# FollowerCounter_60mm_v010.net
KiCad netlist of a schematic drawn in EAGLE
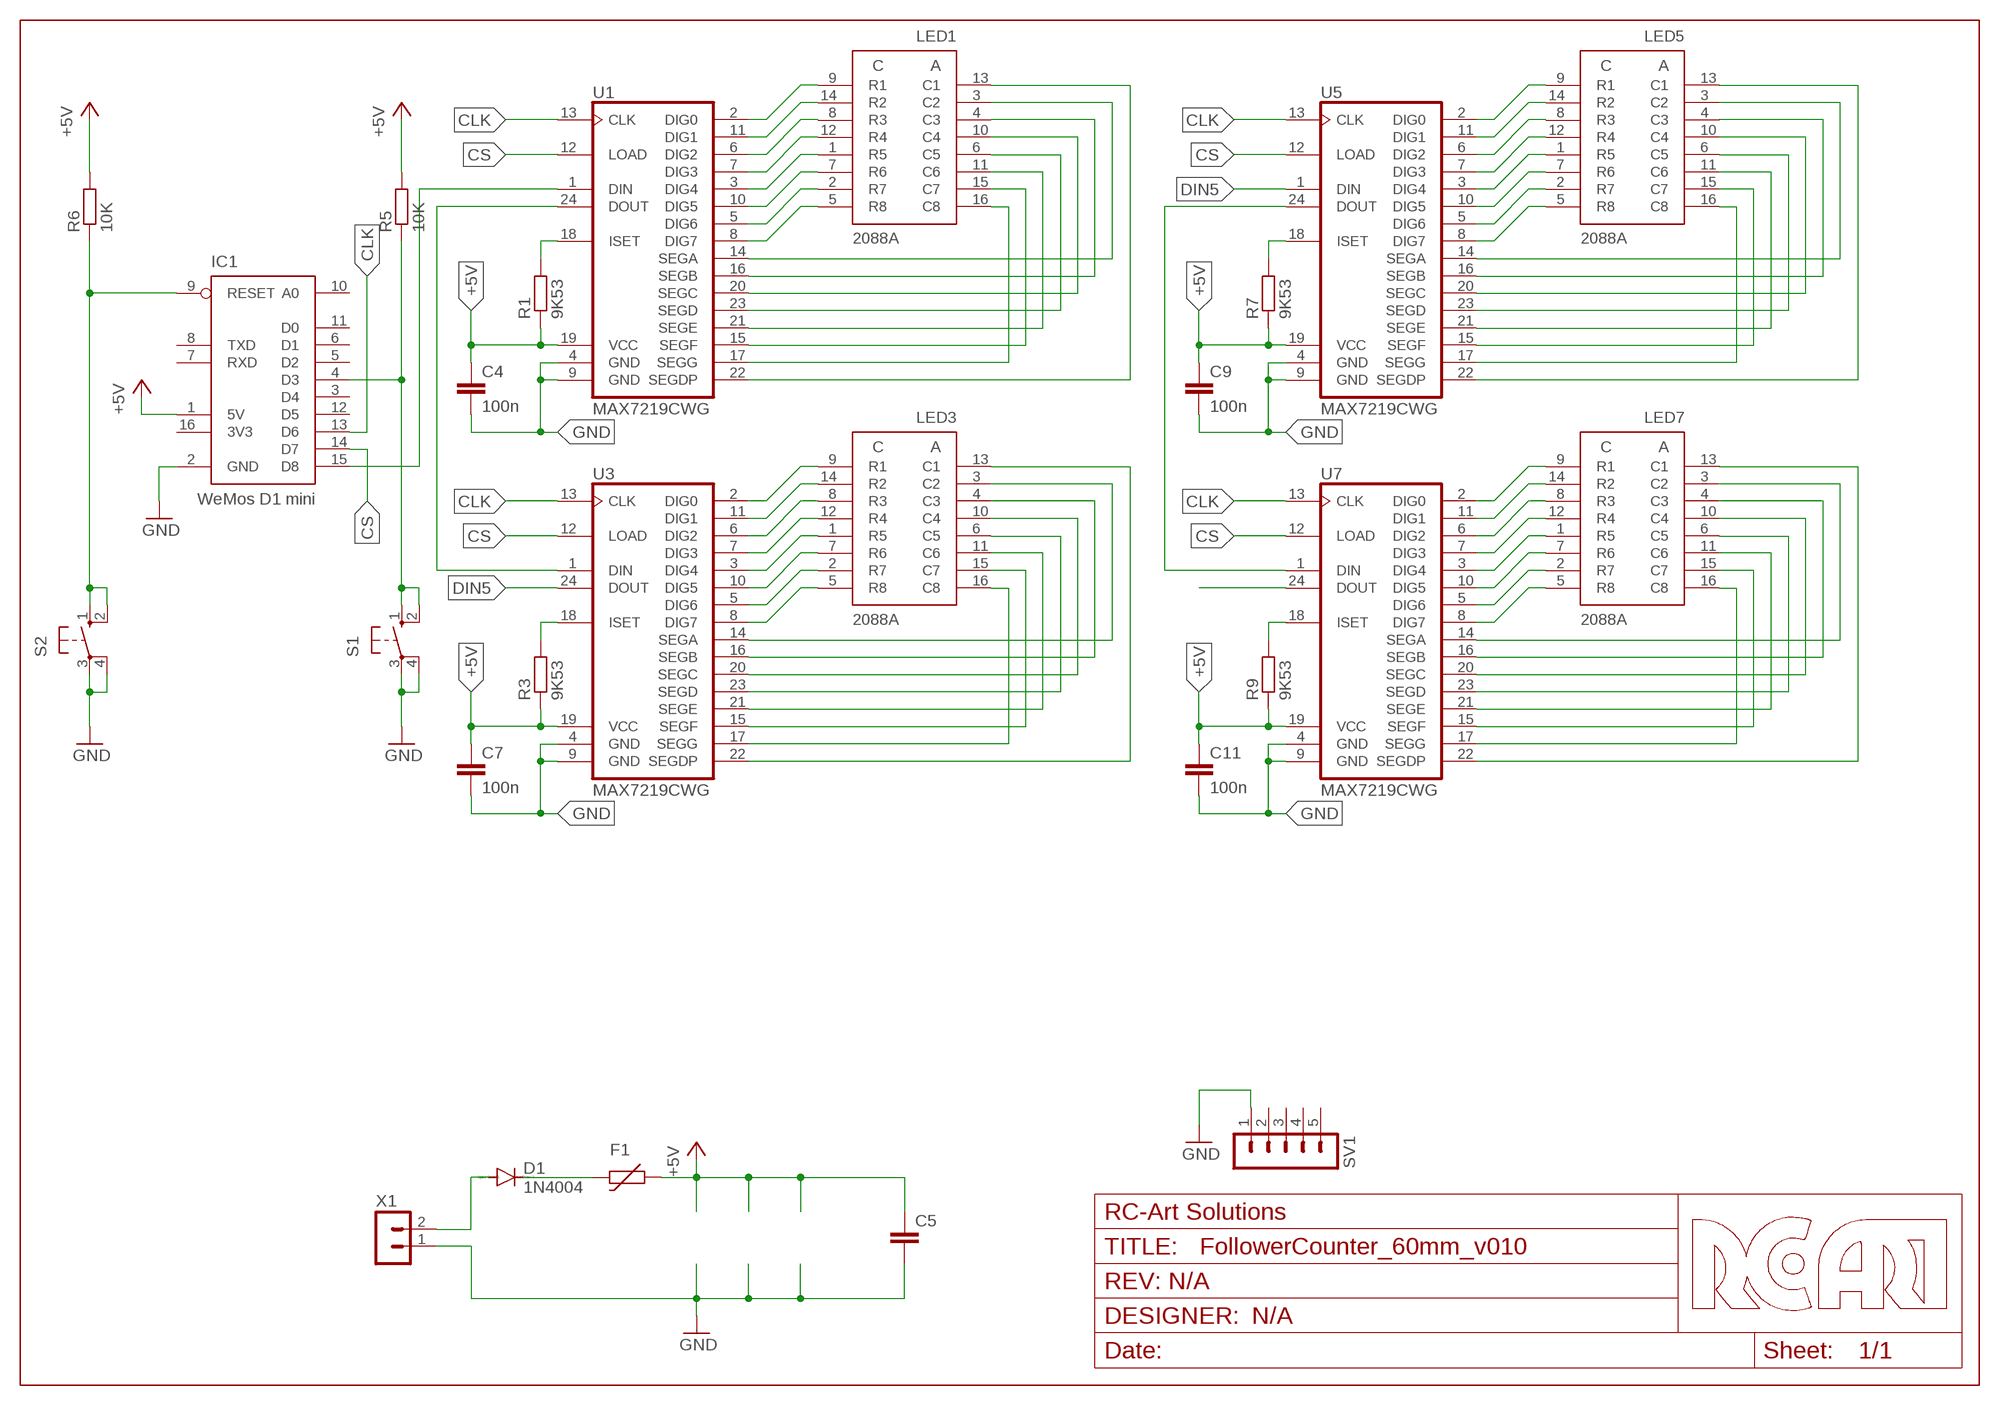
[diagram p0: schematic, sheet 1]

(export (version "E")
  (design (tool "Eeschema 10.0.6"))
  (components
    (comp (ref "C4")
      (value "100n")
      (footprint "eagle-import:C0805")
      (libsource (lib "eagle-import") (part "C-EUC0805"))
    )
    (comp (ref "C5")
      (value "C-EUC0805")
      (footprint "eagle-import:C0805")
      (libsource (lib "eagle-import") (part "C-EUC0805"))
    )
    (comp (ref "C7")
      (value "100n")
      (footprint "eagle-import:C0805")
      (libsource (lib "eagle-import") (part "C-EUC0805"))
    )
    (comp (ref "C9")
      (value "100n")
      (footprint "eagle-import:C0805")
      (libsource (lib "eagle-import") (part "C-EUC0805"))
    )
    (comp (ref "C11")
      (value "100n")
      (footprint "eagle-import:C0805")
      (libsource (lib "eagle-import") (part "C-EUC0805"))
    )
    (comp (ref "D1")
      (value "1N4004")
      (footprint "eagle-import:DO41-10")
      (libsource (lib "eagle-import") (part "1N4004"))
    )
    (comp (ref "F1")
      (value "MF-MSMF075/24-EU")
      (footprint "eagle-import:1812")
      (fields (field (name "MANUFACTURER") "Bourns Inc.") (field (name "PART_NUMBER") "MF-MSMF075/24-2"))
      (libsource (lib "eagle-import") (part "MF-MSMF?-EU075/24"))
    )
    (comp (ref "FRAME1")
      (value "MF_FRAMEDEFAULT")
      (footprint "eagle-import:MF_FRAME_DEFAULT")
      (fields (field (name "REVNUM") "REV: N/A") (field (name "DNAME") "N/A") (field (name "HOUSEPART") "0"))
      (libsource (lib "eagle-import") (part "MF_FRAMEDEFAULT"))
    )
    (comp (ref "IC1")
      (value "WeMos D1 mini")
      (footprint "eagle-import:D1_MINI")
      (libsource (lib "eagle-import") (part "D1_MINI"))
    )
    (comp (ref "LED1")
      (value "2088A")
      (footprint "eagle-import:8X8_60X60")
      (libsource (lib "eagle-import") (part "2088A"))
    )
    (comp (ref "LED3")
      (value "2088A")
      (footprint "eagle-import:8X8_60X60")
      (libsource (lib "eagle-import") (part "2088A"))
    )
    (comp (ref "LED5")
      (value "2088A")
      (footprint "eagle-import:8X8_60X60")
      (libsource (lib "eagle-import") (part "2088A"))
    )
    (comp (ref "LED7")
      (value "2088A")
      (footprint "eagle-import:8X8_60X60")
      (libsource (lib "eagle-import") (part "2088A"))
    )
    (comp (ref "R1")
      (value "9K53")
      (footprint "eagle-import:R0805")
      (libsource (lib "eagle-import") (part "R-EU_R0805"))
    )
    (comp (ref "R3")
      (value "9K53")
      (footprint "eagle-import:R0805")
      (libsource (lib "eagle-import") (part "R-EU_R0805"))
    )
    (comp (ref "R5")
      (value "10K")
      (footprint "eagle-import:R0805")
      (libsource (lib "eagle-import") (part "R-EU_R0805"))
    )
    (comp (ref "R6")
      (value "10K")
      (footprint "eagle-import:R0805")
      (libsource (lib "eagle-import") (part "R-EU_R0805"))
    )
    (comp (ref "R7")
      (value "9K53")
      (footprint "eagle-import:R0805")
      (libsource (lib "eagle-import") (part "R-EU_R0805"))
    )
    (comp (ref "R9")
      (value "9K53")
      (footprint "eagle-import:R0805")
      (libsource (lib "eagle-import") (part "R-EU_R0805"))
    )
    (comp (ref "S1")
      (value "10-XXS")
      (footprint "eagle-import:B3FS-10XX")
      (libsource (lib "eagle-import") (part "10-XXS"))
    )
    (comp (ref "S2")
      (value "10-XXS")
      (footprint "eagle-import:B3FS-10XX")
      (libsource (lib "eagle-import") (part "10-XXS"))
    )
    (comp (ref "SV1")
      (value "MA05-1")
      (footprint "eagle-import:MA05-1")
      (libsource (lib "eagle-import") (part "MA05-1"))
    )
    (comp (ref "U1")
      (value "MAX7219CWG")
      (footprint "eagle-import:SO24L")
      (libsource (lib "eagle-import") (part "MAX7219CWG"))
    )
    (comp (ref "U3")
      (value "MAX7219CWG")
      (footprint "eagle-import:SO24L")
      (libsource (lib "eagle-import") (part "MAX7219CWG"))
    )
    (comp (ref "U5")
      (value "MAX7219CWG")
      (footprint "eagle-import:SO24L")
      (libsource (lib "eagle-import") (part "MAX7219CWG"))
    )
    (comp (ref "U7")
      (value "MAX7219CWG")
      (footprint "eagle-import:SO24L")
      (libsource (lib "eagle-import") (part "MAX7219CWG"))
    )
    (comp (ref "X1")
      (value "MA02-1")
      (footprint "eagle-import:MA02-1")
      (libsource (lib "eagle-import") (part "MA02-1"))
    )
  )
  (nets
    (net (code "1") (name "+5V") (class "Default")
      (node (ref "C11") (pin "1") (pinfunction "1_1") (pintype "passive"))
      (node (ref "C4") (pin "1") (pinfunction "1_1") (pintype "passive"))
      (node (ref "C5") (pin "1") (pinfunction "1_1") (pintype "passive"))
      (node (ref "C7") (pin "1") (pinfunction "1_1") (pintype "passive"))
      (node (ref "C9") (pin "1") (pinfunction "1_1") (pintype "passive"))
      (node (ref "F1") (pin "1") (pinfunction "1_1") (pintype "passive"))
      (node (ref "IC1") (pin "1") (pinfunction "5V_1") (pintype "bidirectional"))
      (node (ref "R1") (pin "1") (pinfunction "1_1") (pintype "passive"))
      (node (ref "R3") (pin "1") (pinfunction "1_1") (pintype "passive"))
      (node (ref "R5") (pin "2") (pinfunction "2_2") (pintype "passive"))
      (node (ref "R6") (pin "2") (pinfunction "2_2") (pintype "passive"))
      (node (ref "R7") (pin "1") (pinfunction "1_1") (pintype "passive"))
      (node (ref "R9") (pin "1") (pinfunction "1_1") (pintype "passive"))
      (node (ref "U1") (pin "19") (pinfunction "VCC_19") (pintype "power_in"))
      (node (ref "U3") (pin "19") (pinfunction "VCC_19") (pintype "power_in"))
      (node (ref "U5") (pin "19") (pinfunction "VCC_19") (pintype "power_in"))
      (node (ref "U7") (pin "19") (pinfunction "VCC_19") (pintype "power_in"))
    )
    (net (code "2") (name "CLK") (class "Default")
      (node (ref "IC1") (pin "13") (pinfunction "D6_13") (pintype "bidirectional"))
      (node (ref "U1") (pin "13") (pinfunction "CLK_13") (pintype "input"))
      (node (ref "U3") (pin "13") (pinfunction "CLK_13") (pintype "input"))
      (node (ref "U5") (pin "13") (pinfunction "CLK_13") (pintype "input"))
      (node (ref "U7") (pin "13") (pinfunction "CLK_13") (pintype "input"))
    )
    (net (code "3") (name "CS") (class "Default")
      (node (ref "IC1") (pin "14") (pinfunction "D7_14") (pintype "bidirectional"))
      (node (ref "U1") (pin "12") (pinfunction "LOAD_12") (pintype "input"))
      (node (ref "U3") (pin "12") (pinfunction "LOAD_12") (pintype "input"))
      (node (ref "U5") (pin "12") (pinfunction "LOAD_12") (pintype "input"))
      (node (ref "U7") (pin "12") (pinfunction "LOAD_12") (pintype "input"))
    )
    (net (code "4") (name "DIN5") (class "Default")
      (node (ref "U3") (pin "24") (pinfunction "DOUT_24") (pintype "output"))
      (node (ref "U5") (pin "1") (pinfunction "DIN_1") (pintype "input"))
    )
    (net (code "5") (name "GND") (class "Default")
      (node (ref "C11") (pin "2") (pinfunction "2_2") (pintype "passive"))
      (node (ref "C4") (pin "2") (pinfunction "2_2") (pintype "passive"))
      (node (ref "C5") (pin "2") (pinfunction "2_2") (pintype "passive"))
      (node (ref "C7") (pin "2") (pinfunction "2_2") (pintype "passive"))
      (node (ref "C9") (pin "2") (pinfunction "2_2") (pintype "passive"))
      (node (ref "IC1") (pin "2") (pinfunction "GND_2") (pintype "bidirectional"))
      (node (ref "S1") (pin "3") (pinfunction "P_3") (pintype "passive"))
      (node (ref "S1") (pin "4") (pinfunction "P1_4") (pintype "passive"))
      (node (ref "S2") (pin "3") (pinfunction "P_3") (pintype "passive"))
      (node (ref "S2") (pin "4") (pinfunction "P1_4") (pintype "passive"))
      (node (ref "SV1") (pin "1") (pinfunction "1_1") (pintype "passive"))
      (node (ref "U1") (pin "4") (pinfunction "GND_4") (pintype "power_in"))
      (node (ref "U1") (pin "9") (pinfunction "GND_9") (pintype "power_in"))
      (node (ref "U3") (pin "4") (pinfunction "GND_4") (pintype "power_in"))
      (node (ref "U3") (pin "9") (pinfunction "GND_9") (pintype "power_in"))
      (node (ref "U5") (pin "4") (pinfunction "GND_4") (pintype "power_in"))
      (node (ref "U5") (pin "9") (pinfunction "GND_9") (pintype "power_in"))
      (node (ref "U7") (pin "4") (pinfunction "GND_4") (pintype "power_in"))
      (node (ref "U7") (pin "9") (pinfunction "GND_9") (pintype "power_in"))
      (node (ref "X1") (pin "1") (pinfunction "1_1") (pintype "passive"))
    )
    (net (code "6") (name "Net-(D1-PadA)") (class "Default")
      (node (ref "D1") (pin "A") (pinfunction "A_A") (pintype "passive"))
      (node (ref "X1") (pin "2") (pinfunction "2_2") (pintype "passive"))
    )
    (net (code "7") (name "Net-(D1-PadC)") (class "Default")
      (node (ref "D1") (pin "C") (pinfunction "C_C") (pintype "passive"))
      (node (ref "F1") (pin "2") (pinfunction "2_2") (pintype "passive"))
    )
    (net (code "8") (name "Net-(IC1-D3)") (class "Default")
      (node (ref "IC1") (pin "4") (pinfunction "D3_4") (pintype "bidirectional"))
      (node (ref "R5") (pin "1") (pinfunction "1_1") (pintype "passive"))
      (node (ref "S1") (pin "1") (pinfunction "S_1") (pintype "passive"))
      (node (ref "S1") (pin "2") (pinfunction "S1_2") (pintype "passive"))
    )
    (net (code "9") (name "Net-(IC1-D8)") (class "Default")
      (node (ref "IC1") (pin "15") (pinfunction "D8_15") (pintype "bidirectional"))
      (node (ref "U1") (pin "1") (pinfunction "DIN_1") (pintype "input"))
    )
    (net (code "10") (name "Net-(IC1-RESET)") (class "Default")
      (node (ref "IC1") (pin "9") (pinfunction "RESET_9") (pintype "bidirectional"))
      (node (ref "R6") (pin "1") (pinfunction "1_1") (pintype "passive"))
      (node (ref "S2") (pin "1") (pinfunction "S_1") (pintype "passive"))
      (node (ref "S2") (pin "2") (pinfunction "S1_2") (pintype "passive"))
    )
    (net (code "11") (name "Net-(LED1-C1)") (class "Default")
      (node (ref "LED1") (pin "13") (pinfunction "C1_13") (pintype "bidirectional"))
      (node (ref "U1") (pin "22") (pinfunction "SEGDP_22") (pintype "output"))
    )
    (net (code "12") (name "Net-(LED1-C2)") (class "Default")
      (node (ref "LED1") (pin "3") (pinfunction "C2_3") (pintype "bidirectional"))
      (node (ref "U1") (pin "14") (pinfunction "SEGA_14") (pintype "output"))
    )
    (net (code "13") (name "Net-(LED1-C3)") (class "Default")
      (node (ref "LED1") (pin "4") (pinfunction "C3_4") (pintype "bidirectional"))
      (node (ref "U1") (pin "16") (pinfunction "SEGB_16") (pintype "output"))
    )
    (net (code "14") (name "Net-(LED1-C4)") (class "Default")
      (node (ref "LED1") (pin "10") (pinfunction "C4_10") (pintype "bidirectional"))
      (node (ref "U1") (pin "20") (pinfunction "SEGC_20") (pintype "output"))
    )
    (net (code "15") (name "Net-(LED1-C5)") (class "Default")
      (node (ref "LED1") (pin "6") (pinfunction "C5_6") (pintype "bidirectional"))
      (node (ref "U1") (pin "23") (pinfunction "SEGD_23") (pintype "output"))
    )
    (net (code "16") (name "Net-(LED1-C6)") (class "Default")
      (node (ref "LED1") (pin "11") (pinfunction "C6_11") (pintype "bidirectional"))
      (node (ref "U1") (pin "21") (pinfunction "SEGE_21") (pintype "output"))
    )
    (net (code "17") (name "Net-(LED1-C7)") (class "Default")
      (node (ref "LED1") (pin "15") (pinfunction "C7_15") (pintype "bidirectional"))
      (node (ref "U1") (pin "15") (pinfunction "SEGF_15") (pintype "output"))
    )
    (net (code "18") (name "Net-(LED1-C8)") (class "Default")
      (node (ref "LED1") (pin "16") (pinfunction "C8_16") (pintype "bidirectional"))
      (node (ref "U1") (pin "17") (pinfunction "SEGG_17") (pintype "output"))
    )
    (net (code "19") (name "Net-(LED1-R1)") (class "Default")
      (node (ref "LED1") (pin "9") (pinfunction "R1_9") (pintype "bidirectional"))
      (node (ref "U1") (pin "2") (pinfunction "DIG0_2") (pintype "output"))
    )
    (net (code "20") (name "Net-(LED1-R2)") (class "Default")
      (node (ref "LED1") (pin "14") (pinfunction "R2_14") (pintype "bidirectional"))
      (node (ref "U1") (pin "11") (pinfunction "DIG1_11") (pintype "output"))
    )
    (net (code "21") (name "Net-(LED1-R3)") (class "Default")
      (node (ref "LED1") (pin "8") (pinfunction "R3_8") (pintype "bidirectional"))
      (node (ref "U1") (pin "6") (pinfunction "DIG2_6") (pintype "output"))
    )
    (net (code "22") (name "Net-(LED1-R4)") (class "Default")
      (node (ref "LED1") (pin "12") (pinfunction "R4_12") (pintype "bidirectional"))
      (node (ref "U1") (pin "7") (pinfunction "DIG3_7") (pintype "output"))
    )
    (net (code "23") (name "Net-(LED1-R5)") (class "Default")
      (node (ref "LED1") (pin "1") (pinfunction "R5_1") (pintype "bidirectional"))
      (node (ref "U1") (pin "3") (pinfunction "DIG4_3") (pintype "output"))
    )
    (net (code "24") (name "Net-(LED1-R6)") (class "Default")
      (node (ref "LED1") (pin "7") (pinfunction "R6_7") (pintype "bidirectional"))
      (node (ref "U1") (pin "10") (pinfunction "DIG5_10") (pintype "output"))
    )
    (net (code "25") (name "Net-(LED1-R7)") (class "Default")
      (node (ref "LED1") (pin "2") (pinfunction "R7_2") (pintype "bidirectional"))
      (node (ref "U1") (pin "5") (pinfunction "DIG6_5") (pintype "output"))
    )
    (net (code "26") (name "Net-(LED1-R8)") (class "Default")
      (node (ref "LED1") (pin "5") (pinfunction "R8_5") (pintype "bidirectional"))
      (node (ref "U1") (pin "8") (pinfunction "DIG7_8") (pintype "output"))
    )
    (net (code "27") (name "Net-(LED3-C1)") (class "Default")
      (node (ref "LED3") (pin "13") (pinfunction "C1_13") (pintype "bidirectional"))
      (node (ref "U3") (pin "22") (pinfunction "SEGDP_22") (pintype "output"))
    )
    (net (code "28") (name "Net-(LED3-C2)") (class "Default")
      (node (ref "LED3") (pin "3") (pinfunction "C2_3") (pintype "bidirectional"))
      (node (ref "U3") (pin "14") (pinfunction "SEGA_14") (pintype "output"))
    )
    (net (code "29") (name "Net-(LED3-C3)") (class "Default")
      (node (ref "LED3") (pin "4") (pinfunction "C3_4") (pintype "bidirectional"))
      (node (ref "U3") (pin "16") (pinfunction "SEGB_16") (pintype "output"))
    )
    (net (code "30") (name "Net-(LED3-C4)") (class "Default")
      (node (ref "LED3") (pin "10") (pinfunction "C4_10") (pintype "bidirectional"))
      (node (ref "U3") (pin "20") (pinfunction "SEGC_20") (pintype "output"))
    )
    (net (code "31") (name "Net-(LED3-C5)") (class "Default")
      (node (ref "LED3") (pin "6") (pinfunction "C5_6") (pintype "bidirectional"))
      (node (ref "U3") (pin "23") (pinfunction "SEGD_23") (pintype "output"))
    )
    (net (code "32") (name "Net-(LED3-C6)") (class "Default")
      (node (ref "LED3") (pin "11") (pinfunction "C6_11") (pintype "bidirectional"))
      (node (ref "U3") (pin "21") (pinfunction "SEGE_21") (pintype "output"))
    )
    (net (code "33") (name "Net-(LED3-C7)") (class "Default")
      (node (ref "LED3") (pin "15") (pinfunction "C7_15") (pintype "bidirectional"))
      (node (ref "U3") (pin "15") (pinfunction "SEGF_15") (pintype "output"))
    )
    (net (code "34") (name "Net-(LED3-C8)") (class "Default")
      (node (ref "LED3") (pin "16") (pinfunction "C8_16") (pintype "bidirectional"))
      (node (ref "U3") (pin "17") (pinfunction "SEGG_17") (pintype "output"))
    )
    (net (code "35") (name "Net-(LED3-R1)") (class "Default")
      (node (ref "LED3") (pin "9") (pinfunction "R1_9") (pintype "bidirectional"))
      (node (ref "U3") (pin "2") (pinfunction "DIG0_2") (pintype "output"))
    )
    (net (code "36") (name "Net-(LED3-R2)") (class "Default")
      (node (ref "LED3") (pin "14") (pinfunction "R2_14") (pintype "bidirectional"))
      (node (ref "U3") (pin "11") (pinfunction "DIG1_11") (pintype "output"))
    )
    (net (code "37") (name "Net-(LED3-R3)") (class "Default")
      (node (ref "LED3") (pin "8") (pinfunction "R3_8") (pintype "bidirectional"))
      (node (ref "U3") (pin "6") (pinfunction "DIG2_6") (pintype "output"))
    )
    (net (code "38") (name "Net-(LED3-R4)") (class "Default")
      (node (ref "LED3") (pin "12") (pinfunction "R4_12") (pintype "bidirectional"))
      (node (ref "U3") (pin "7") (pinfunction "DIG3_7") (pintype "output"))
    )
    (net (code "39") (name "Net-(LED3-R5)") (class "Default")
      (node (ref "LED3") (pin "1") (pinfunction "R5_1") (pintype "bidirectional"))
      (node (ref "U3") (pin "3") (pinfunction "DIG4_3") (pintype "output"))
    )
    (net (code "40") (name "Net-(LED3-R6)") (class "Default")
      (node (ref "LED3") (pin "7") (pinfunction "R6_7") (pintype "bidirectional"))
      (node (ref "U3") (pin "10") (pinfunction "DIG5_10") (pintype "output"))
    )
    (net (code "41") (name "Net-(LED3-R7)") (class "Default")
      (node (ref "LED3") (pin "2") (pinfunction "R7_2") (pintype "bidirectional"))
      (node (ref "U3") (pin "5") (pinfunction "DIG6_5") (pintype "output"))
    )
    (net (code "42") (name "Net-(LED3-R8)") (class "Default")
      (node (ref "LED3") (pin "5") (pinfunction "R8_5") (pintype "bidirectional"))
      (node (ref "U3") (pin "8") (pinfunction "DIG7_8") (pintype "output"))
    )
    (net (code "43") (name "Net-(LED5-C1)") (class "Default")
      (node (ref "LED5") (pin "13") (pinfunction "C1_13") (pintype "bidirectional"))
      (node (ref "U5") (pin "22") (pinfunction "SEGDP_22") (pintype "output"))
    )
    (net (code "44") (name "Net-(LED5-C2)") (class "Default")
      (node (ref "LED5") (pin "3") (pinfunction "C2_3") (pintype "bidirectional"))
      (node (ref "U5") (pin "14") (pinfunction "SEGA_14") (pintype "output"))
    )
    (net (code "45") (name "Net-(LED5-C3)") (class "Default")
      (node (ref "LED5") (pin "4") (pinfunction "C3_4") (pintype "bidirectional"))
      (node (ref "U5") (pin "16") (pinfunction "SEGB_16") (pintype "output"))
    )
    (net (code "46") (name "Net-(LED5-C4)") (class "Default")
      (node (ref "LED5") (pin "10") (pinfunction "C4_10") (pintype "bidirectional"))
      (node (ref "U5") (pin "20") (pinfunction "SEGC_20") (pintype "output"))
    )
    (net (code "47") (name "Net-(LED5-C5)") (class "Default")
      (node (ref "LED5") (pin "6") (pinfunction "C5_6") (pintype "bidirectional"))
      (node (ref "U5") (pin "23") (pinfunction "SEGD_23") (pintype "output"))
    )
    (net (code "48") (name "Net-(LED5-C6)") (class "Default")
      (node (ref "LED5") (pin "11") (pinfunction "C6_11") (pintype "bidirectional"))
      (node (ref "U5") (pin "21") (pinfunction "SEGE_21") (pintype "output"))
    )
    (net (code "49") (name "Net-(LED5-C7)") (class "Default")
      (node (ref "LED5") (pin "15") (pinfunction "C7_15") (pintype "bidirectional"))
      (node (ref "U5") (pin "15") (pinfunction "SEGF_15") (pintype "output"))
    )
    (net (code "50") (name "Net-(LED5-C8)") (class "Default")
      (node (ref "LED5") (pin "16") (pinfunction "C8_16") (pintype "bidirectional"))
      (node (ref "U5") (pin "17") (pinfunction "SEGG_17") (pintype "output"))
    )
    (net (code "51") (name "Net-(LED5-R1)") (class "Default")
      (node (ref "LED5") (pin "9") (pinfunction "R1_9") (pintype "bidirectional"))
      (node (ref "U5") (pin "2") (pinfunction "DIG0_2") (pintype "output"))
    )
    (net (code "52") (name "Net-(LED5-R2)") (class "Default")
      (node (ref "LED5") (pin "14") (pinfunction "R2_14") (pintype "bidirectional"))
      (node (ref "U5") (pin "11") (pinfunction "DIG1_11") (pintype "output"))
    )
    (net (code "53") (name "Net-(LED5-R3)") (class "Default")
      (node (ref "LED5") (pin "8") (pinfunction "R3_8") (pintype "bidirectional"))
      (node (ref "U5") (pin "6") (pinfunction "DIG2_6") (pintype "output"))
    )
    (net (code "54") (name "Net-(LED5-R4)") (class "Default")
      (node (ref "LED5") (pin "12") (pinfunction "R4_12") (pintype "bidirectional"))
      (node (ref "U5") (pin "7") (pinfunction "DIG3_7") (pintype "output"))
    )
    (net (code "55") (name "Net-(LED5-R5)") (class "Default")
      (node (ref "LED5") (pin "1") (pinfunction "R5_1") (pintype "bidirectional"))
      (node (ref "U5") (pin "3") (pinfunction "DIG4_3") (pintype "output"))
    )
    (net (code "56") (name "Net-(LED5-R6)") (class "Default")
      (node (ref "LED5") (pin "7") (pinfunction "R6_7") (pintype "bidirectional"))
      (node (ref "U5") (pin "10") (pinfunction "DIG5_10") (pintype "output"))
    )
    (net (code "57") (name "Net-(LED5-R7)") (class "Default")
      (node (ref "LED5") (pin "2") (pinfunction "R7_2") (pintype "bidirectional"))
      (node (ref "U5") (pin "5") (pinfunction "DIG6_5") (pintype "output"))
    )
    (net (code "58") (name "Net-(LED5-R8)") (class "Default")
      (node (ref "LED5") (pin "5") (pinfunction "R8_5") (pintype "bidirectional"))
      (node (ref "U5") (pin "8") (pinfunction "DIG7_8") (pintype "output"))
    )
    (net (code "59") (name "Net-(LED7-C1)") (class "Default")
      (node (ref "LED7") (pin "13") (pinfunction "C1_13") (pintype "bidirectional"))
      (node (ref "U7") (pin "22") (pinfunction "SEGDP_22") (pintype "output"))
    )
    (net (code "60") (name "Net-(LED7-C2)") (class "Default")
      (node (ref "LED7") (pin "3") (pinfunction "C2_3") (pintype "bidirectional"))
      (node (ref "U7") (pin "14") (pinfunction "SEGA_14") (pintype "output"))
    )
    (net (code "61") (name "Net-(LED7-C3)") (class "Default")
      (node (ref "LED7") (pin "4") (pinfunction "C3_4") (pintype "bidirectional"))
      (node (ref "U7") (pin "16") (pinfunction "SEGB_16") (pintype "output"))
    )
    (net (code "62") (name "Net-(LED7-C4)") (class "Default")
      (node (ref "LED7") (pin "10") (pinfunction "C4_10") (pintype "bidirectional"))
      (node (ref "U7") (pin "20") (pinfunction "SEGC_20") (pintype "output"))
    )
    (net (code "63") (name "Net-(LED7-C5)") (class "Default")
      (node (ref "LED7") (pin "6") (pinfunction "C5_6") (pintype "bidirectional"))
      (node (ref "U7") (pin "23") (pinfunction "SEGD_23") (pintype "output"))
    )
    (net (code "64") (name "Net-(LED7-C6)") (class "Default")
      (node (ref "LED7") (pin "11") (pinfunction "C6_11") (pintype "bidirectional"))
      (node (ref "U7") (pin "21") (pinfunction "SEGE_21") (pintype "output"))
    )
    (net (code "65") (name "Net-(LED7-C7)") (class "Default")
      (node (ref "LED7") (pin "15") (pinfunction "C7_15") (pintype "bidirectional"))
      (node (ref "U7") (pin "15") (pinfunction "SEGF_15") (pintype "output"))
    )
    (net (code "66") (name "Net-(LED7-C8)") (class "Default")
      (node (ref "LED7") (pin "16") (pinfunction "C8_16") (pintype "bidirectional"))
      (node (ref "U7") (pin "17") (pinfunction "SEGG_17") (pintype "output"))
    )
    (net (code "67") (name "Net-(LED7-R1)") (class "Default")
      (node (ref "LED7") (pin "9") (pinfunction "R1_9") (pintype "bidirectional"))
      (node (ref "U7") (pin "2") (pinfunction "DIG0_2") (pintype "output"))
    )
    (net (code "68") (name "Net-(LED7-R2)") (class "Default")
      (node (ref "LED7") (pin "14") (pinfunction "R2_14") (pintype "bidirectional"))
      (node (ref "U7") (pin "11") (pinfunction "DIG1_11") (pintype "output"))
    )
    (net (code "69") (name "Net-(LED7-R3)") (class "Default")
      (node (ref "LED7") (pin "8") (pinfunction "R3_8") (pintype "bidirectional"))
      (node (ref "U7") (pin "6") (pinfunction "DIG2_6") (pintype "output"))
    )
    (net (code "70") (name "Net-(LED7-R4)") (class "Default")
      (node (ref "LED7") (pin "12") (pinfunction "R4_12") (pintype "bidirectional"))
      (node (ref "U7") (pin "7") (pinfunction "DIG3_7") (pintype "output"))
    )
    (net (code "71") (name "Net-(LED7-R5)") (class "Default")
      (node (ref "LED7") (pin "1") (pinfunction "R5_1") (pintype "bidirectional"))
      (node (ref "U7") (pin "3") (pinfunction "DIG4_3") (pintype "output"))
    )
    (net (code "72") (name "Net-(LED7-R6)") (class "Default")
      (node (ref "LED7") (pin "7") (pinfunction "R6_7") (pintype "bidirectional"))
      (node (ref "U7") (pin "10") (pinfunction "DIG5_10") (pintype "output"))
    )
    (net (code "73") (name "Net-(LED7-R7)") (class "Default")
      (node (ref "LED7") (pin "2") (pinfunction "R7_2") (pintype "bidirectional"))
      (node (ref "U7") (pin "5") (pinfunction "DIG6_5") (pintype "output"))
    )
    (net (code "74") (name "Net-(LED7-R8)") (class "Default")
      (node (ref "LED7") (pin "5") (pinfunction "R8_5") (pintype "bidirectional"))
      (node (ref "U7") (pin "8") (pinfunction "DIG7_8") (pintype "output"))
    )
    (net (code "75") (name "Net-(U1-DOUT)") (class "Default")
      (node (ref "U1") (pin "24") (pinfunction "DOUT_24") (pintype "output"))
      (node (ref "U3") (pin "1") (pinfunction "DIN_1") (pintype "input"))
    )
    (net (code "76") (name "Net-(U1-ISET)") (class "Default")
      (node (ref "R1") (pin "2") (pinfunction "2_2") (pintype "passive"))
      (node (ref "U1") (pin "18") (pinfunction "ISET_18") (pintype "input"))
    )
    (net (code "77") (name "Net-(U3-ISET)") (class "Default")
      (node (ref "R3") (pin "2") (pinfunction "2_2") (pintype "passive"))
      (node (ref "U3") (pin "18") (pinfunction "ISET_18") (pintype "input"))
    )
    (net (code "78") (name "Net-(U5-DOUT)") (class "Default")
      (node (ref "U5") (pin "24") (pinfunction "DOUT_24") (pintype "output"))
      (node (ref "U7") (pin "1") (pinfunction "DIN_1") (pintype "input"))
    )
    (net (code "79") (name "Net-(U5-ISET)") (class "Default")
      (node (ref "R7") (pin "2") (pinfunction "2_2") (pintype "passive"))
      (node (ref "U5") (pin "18") (pinfunction "ISET_18") (pintype "input"))
    )
    (net (code "80") (name "Net-(U7-ISET)") (class "Default")
      (node (ref "R9") (pin "2") (pinfunction "2_2") (pintype "passive"))
      (node (ref "U7") (pin "18") (pinfunction "ISET_18") (pintype "input"))
    )
    (net (code "81") (name "unconnected-(IC1-3V3-Pad16)") (class "Default")
      (node (ref "IC1") (pin "16") (pinfunction "3V3_16") (pintype "bidirectional"))
    )
    (net (code "82") (name "unconnected-(IC1-A0-Pad10)") (class "Default")
      (node (ref "IC1") (pin "10") (pinfunction "A0_10") (pintype "bidirectional"))
    )
    (net (code "83") (name "unconnected-(IC1-D0-Pad11)") (class "Default")
      (node (ref "IC1") (pin "11") (pinfunction "D0_11") (pintype "bidirectional"))
    )
    (net (code "84") (name "unconnected-(IC1-D1-Pad6)") (class "Default")
      (node (ref "IC1") (pin "6") (pinfunction "D1_6") (pintype "bidirectional"))
    )
    (net (code "85") (name "unconnected-(IC1-D2-Pad5)") (class "Default")
      (node (ref "IC1") (pin "5") (pinfunction "D2_5") (pintype "bidirectional"))
    )
    (net (code "86") (name "unconnected-(IC1-D4-Pad3)") (class "Default")
      (node (ref "IC1") (pin "3") (pinfunction "D4_3") (pintype "bidirectional"))
    )
    (net (code "87") (name "unconnected-(IC1-D5-Pad12)") (class "Default")
      (node (ref "IC1") (pin "12") (pinfunction "D5_12") (pintype "bidirectional"))
    )
    (net (code "88") (name "unconnected-(IC1-RXD-Pad7)") (class "Default")
      (node (ref "IC1") (pin "7") (pinfunction "RXD_7") (pintype "bidirectional"))
    )
    (net (code "89") (name "unconnected-(IC1-TXD-Pad8)") (class "Default")
      (node (ref "IC1") (pin "8") (pinfunction "TXD_8") (pintype "bidirectional"))
    )
    (net (code "90") (name "unconnected-(SV1-Pad2)") (class "Default")
      (node (ref "SV1") (pin "2") (pinfunction "2_2") (pintype "passive"))
    )
    (net (code "91") (name "unconnected-(SV1-Pad3)") (class "Default")
      (node (ref "SV1") (pin "3") (pinfunction "3_3") (pintype "passive"))
    )
    (net (code "92") (name "unconnected-(SV1-Pad4)") (class "Default")
      (node (ref "SV1") (pin "4") (pinfunction "4_4") (pintype "passive"))
    )
    (net (code "93") (name "unconnected-(SV1-Pad5)") (class "Default")
      (node (ref "SV1") (pin "5") (pinfunction "5_5") (pintype "passive"))
    )
    (net (code "94") (name "unconnected-(U7-DOUT-Pad24)") (class "Default")
      (node (ref "U7") (pin "24") (pinfunction "DOUT_24") (pintype "output"))
    )
  )
)
